# TMP235AQDB2TQ1.net
KiCad netlist of a schematic drawn in Altium Designer
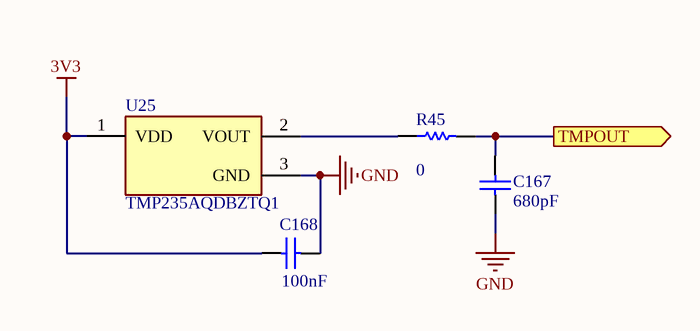
[diagram p0: TMP235AQDB2TQ1.SchDoc]

(export (version "E")
  (design (tool "Eeschema 10.0.6"))
  (components
    (comp (ref "C167")
      (value "680pF")
      (footprint "0402-A")
      (description "Capacitor")
      (fields (field (name "Comment") "Cap") (field (name "PUBLISHER") "Altium Limited"))
      (libsource (lib "Miscellaneous Devices") (part "Cap"))
    )
    (comp (ref "C168")
      (value "100nF")
      (footprint "0402-A")
      (description "Capacitor")
      (fields (field (name "Comment") "Cap") (field (name "PUBLISHER") "Altium Limited"))
      (libsource (lib "Miscellaneous Devices") (part "Cap"))
    )
    (comp (ref "R45")
      (value "0")
      (footprint "0402-A")
      (description "Resistor")
      (fields (field (name "Comment") "Res1") (field (name "PUBLISHER") "Altium Limited"))
      (libsource (lib "Miscellaneous Devices") (part "Res1"))
    )
    (comp (ref "U25")
      (value "TMP235AQDBZTQ1")
      (footprint "FP-DBZ0003A-MFG")
      (description "LOW-POWER HIGH-ACCURACY ANALOG O")
      (fields
        (field (name "MANUFACTURER") "Texas Instruments")
        (field (name "MANUFACTURER PART NUMBER") "TMP235A2DBZR")
      )
      (libsource (lib "Altium Content Vault") (part "1212246baba8f64ab0dd7b63bd818eb"))
    )
  )
  (nets
    (net (code "1") (name "/TMPOUT") (class "Default")
      (node (ref "C167") (pin "1") (pinfunction "1_1") (pintype "passive"))
      (node (ref "R45") (pin "2") (pinfunction "2_2") (pintype "passive"))
    )
    (net (code "2") (name "3V3") (class "Default")
      (node (ref "C168") (pin "1") (pinfunction "1_1") (pintype "passive"))
      (node (ref "U25") (pin "1") (pinfunction "VDD_1") (pintype "power_in"))
    )
    (net (code "3") (name "GND") (class "Default")
      (node (ref "C167") (pin "2") (pinfunction "2_2") (pintype "passive"))
      (node (ref "C168") (pin "2") (pinfunction "2_2") (pintype "passive"))
      (node (ref "U25") (pin "3") (pinfunction "GND_3") (pintype "power_in"))
    )
    (net (code "4") (name "Net-(U25-VOUT)") (class "Default")
      (node (ref "R45") (pin "1") (pinfunction "1_1") (pintype "passive"))
      (node (ref "U25") (pin "2") (pinfunction "VOUT_2") (pintype "passive"))
    )
  )
)
